# odbiornik.net
KiCad netlist of a schematic drawn in EAGLE
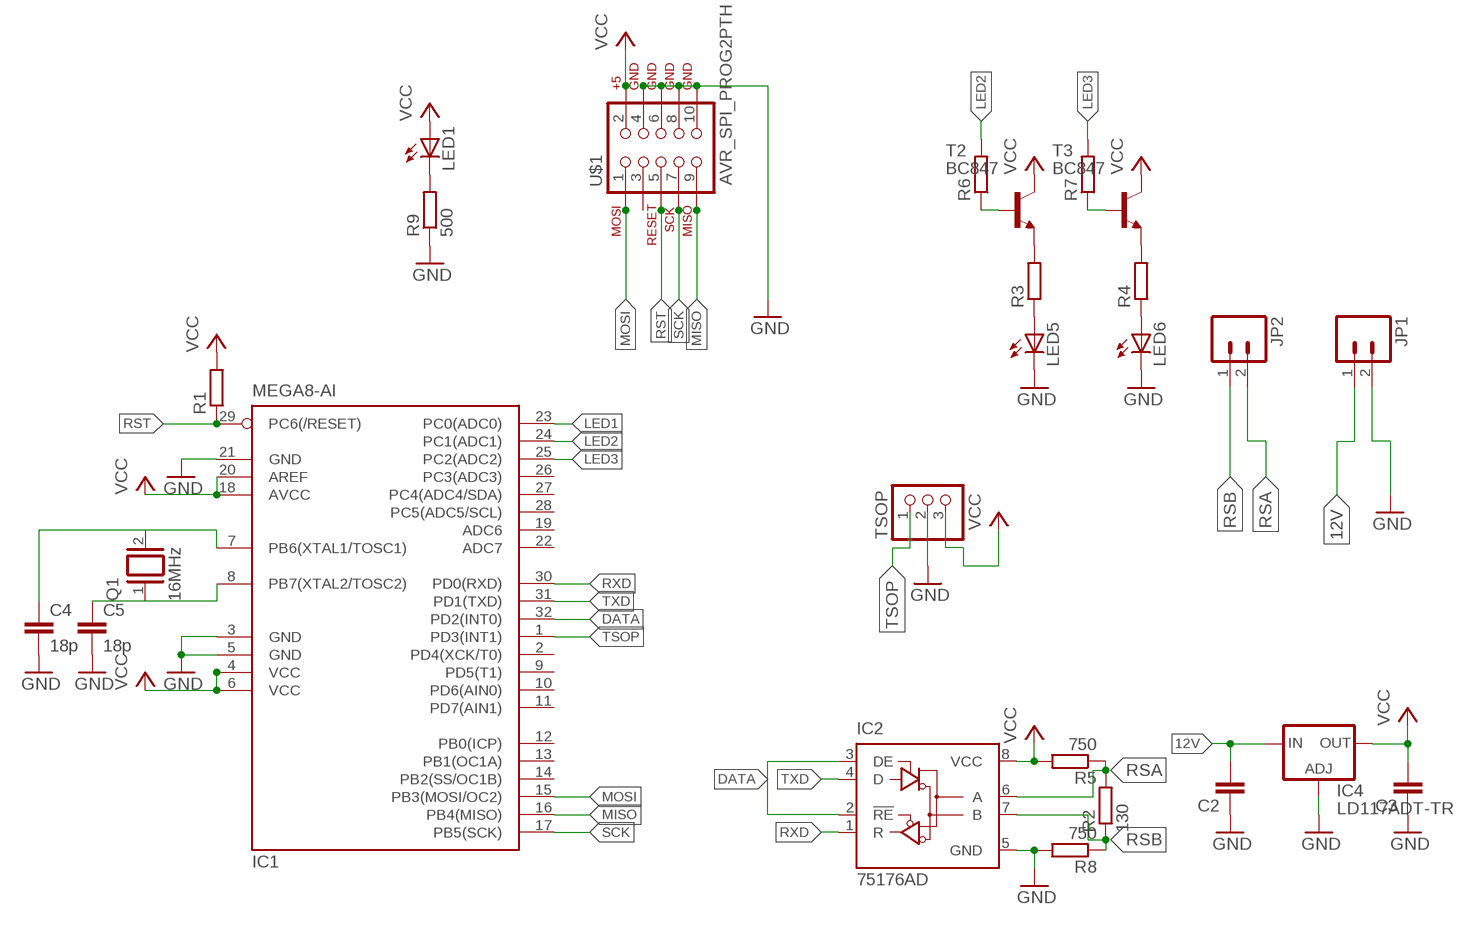
[diagram p0: schematic, sheet 1]

(export (version "E")
  (design (tool "Eeschema 10.0.6"))
  (components
    (comp (ref "C2")
      (value "C-EUC0805")
      (footprint "eagle-import:C0805")
      (libsource (lib "eagle-import") (part "C-EUC0805"))
    )
    (comp (ref "C3")
      (value "C-EUC0805")
      (footprint "eagle-import:C0805")
      (libsource (lib "eagle-import") (part "C-EUC0805"))
    )
    (comp (ref "C4")
      (value "18p")
      (footprint "eagle-import:C0805")
      (libsource (lib "eagle-import") (part "C-EUC0805"))
    )
    (comp (ref "C5")
      (value "18p")
      (footprint "eagle-import:C0805")
      (libsource (lib "eagle-import") (part "C-EUC0805"))
    )
    (comp (ref "IC1")
      (value "MEGA8-AI")
      (footprint "eagle-import:TQFP32-08")
      (fields (field (name "MPN") "ATMEGA8-16AU"))
      (libsource (lib "eagle-import") (part "MEGA8-AI"))
    )
    (comp (ref "IC2")
      (value "75176AD")
      (footprint "eagle-import:D_R-PDSO-G8")
      (libsource (lib "eagle-import") (part "75176AD"))
    )
    (comp (ref "IC4")
      (value "LD117ADT-TR")
      (footprint "eagle-import:DPACK")
      (libsource (lib "eagle-import") (part "LD117A?DT-TR"))
    )
    (comp (ref "JP1")
      (value "M02LOCK_LONGPADS")
      (footprint "eagle-import:1X02_LOCK_LONGPADS")
      (libsource (lib "eagle-import") (part "M02LOCK_LONGPADS"))
    )
    (comp (ref "JP2")
      (value "M02LOCK_LONGPADS")
      (footprint "eagle-import:1X02_LOCK_LONGPADS")
      (libsource (lib "eagle-import") (part "M02LOCK_LONGPADS"))
    )
    (comp (ref "LED1")
      (value "LED1206")
      (footprint "eagle-import:LED-1206")
      (libsource (lib "eagle-import") (part "LED1206"))
    )
    (comp (ref "LED5")
      (value "LEDSFH480")
      (footprint "eagle-import:SFH480")
      (libsource (lib "eagle-import") (part "LEDSFH480"))
    )
    (comp (ref "LED6")
      (value "LEDSFH480")
      (footprint "eagle-import:SFH480")
      (libsource (lib "eagle-import") (part "LEDSFH480"))
    )
    (comp (ref "Q1")
      (value "16MHz")
      (footprint "eagle-import:QS")
      (libsource (lib "eagle-import") (part "XTAL/S"))
    )
    (comp (ref "R1")
      (value "R-EU_R0805")
      (footprint "eagle-import:R0805")
      (libsource (lib "eagle-import") (part "R-EU_R0805"))
    )
    (comp (ref "R2")
      (value "130")
      (footprint "eagle-import:R0805")
      (libsource (lib "eagle-import") (part "R-EU_R0805"))
    )
    (comp (ref "R3")
      (value "R-EU_R0805")
      (footprint "eagle-import:R0805")
      (libsource (lib "eagle-import") (part "R-EU_R0805"))
    )
    (comp (ref "R4")
      (value "R-EU_R0805")
      (footprint "eagle-import:R0805")
      (libsource (lib "eagle-import") (part "R-EU_R0805"))
    )
    (comp (ref "R5")
      (value "750")
      (footprint "eagle-import:R0805")
      (libsource (lib "eagle-import") (part "R-EU_R0805"))
    )
    (comp (ref "R6")
      (value "R-EU_R0805")
      (footprint "eagle-import:R0805")
      (libsource (lib "eagle-import") (part "R-EU_R0805"))
    )
    (comp (ref "R7")
      (value "R-EU_R0805")
      (footprint "eagle-import:R0805")
      (libsource (lib "eagle-import") (part "R-EU_R0805"))
    )
    (comp (ref "R8")
      (value "750")
      (footprint "eagle-import:R0805")
      (libsource (lib "eagle-import") (part "R-EU_R0805"))
    )
    (comp (ref "R9")
      (value "500")
      (footprint "eagle-import:R0805")
      (libsource (lib "eagle-import") (part "R-EU_R0805"))
    )
    (comp (ref "T2")
      (value "BC847")
      (footprint "eagle-import:SOT23")
      (libsource (lib "eagle-import") (part "BC847"))
    )
    (comp (ref "T3")
      (value "BC847")
      (footprint "eagle-import:SOT23")
      (libsource (lib "eagle-import") (part "BC847"))
    )
    (comp (ref "TSOP")
      (value "PINHD-1X3")
      (footprint "eagle-import:1X03")
      (libsource (lib "eagle-import") (part "PINHD-1X3"))
    )
    (comp (ref "U$1")
      (value "AVR_SPI_PROG2PTH")
      (footprint "eagle-import:AVR_ICSP")
      (libsource (lib "eagle-import") (part "AVR_SPI_PROG2PTH"))
    )
  )
  (nets
    (net (code "1") (name "12V") (class "Default")
      (node (ref "C2") (pin "2") (pinfunction "2_2") (pintype "passive"))
      (node (ref "IC4") (pin "3") (pinfunction "IN_3") (pintype "input"))
      (node (ref "JP1") (pin "1") (pinfunction "1_1") (pintype "passive"))
    )
    (net (code "2") (name "DATA") (class "Default")
      (node (ref "IC1") (pin "32") (pinfunction "PD2(INT0)_32") (pintype "bidirectional"))
      (node (ref "IC2") (pin "2") (pinfunction "~{RE}_2") (pintype "input"))
      (node (ref "IC2") (pin "3") (pinfunction "DE_3") (pintype "input"))
    )
    (net (code "3") (name "GND") (class "Default")
      (node (ref "C2") (pin "1") (pinfunction "1_1") (pintype "passive"))
      (node (ref "C3") (pin "1") (pinfunction "1_1") (pintype "passive"))
      (node (ref "C4") (pin "2") (pinfunction "2_2") (pintype "passive"))
      (node (ref "C5") (pin "2") (pinfunction "2_2") (pintype "passive"))
      (node (ref "IC1") (pin "21") (pinfunction "GND_21") (pintype "power_in"))
      (node (ref "IC1") (pin "3") (pinfunction "GND_3") (pintype "power_in"))
      (node (ref "IC1") (pin "5") (pinfunction "GND_5") (pintype "power_in"))
      (node (ref "IC2") (pin "5") (pinfunction "GND_5") (pintype "power_in"))
      (node (ref "IC4") (pin "1") (pinfunction "ADJ_1") (pintype "input"))
      (node (ref "JP1") (pin "2") (pinfunction "2_2") (pintype "passive"))
      (node (ref "LED5") (pin "K") (pinfunction "C_K") (pintype "passive"))
      (node (ref "LED6") (pin "K") (pinfunction "C_K") (pintype "passive"))
      (node (ref "R8") (pin "2") (pinfunction "2_2") (pintype "passive"))
      (node (ref "R9") (pin "1") (pinfunction "1_1") (pintype "passive"))
      (node (ref "TSOP") (pin "2") (pinfunction "2_2") (pintype "passive"))
      (node (ref "U$1") (pin "10") (pinfunction "10_10") (pintype "passive"))
      (node (ref "U$1") (pin "4") (pinfunction "4_4") (pintype "passive"))
      (node (ref "U$1") (pin "6") (pinfunction "6_6") (pintype "passive"))
      (node (ref "U$1") (pin "8") (pinfunction "8_8") (pintype "passive"))
    )
    (net (code "4") (name "LED1") (class "Default")
      (node (ref "IC1") (pin "23") (pinfunction "PC0(ADC0)_23") (pintype "bidirectional"))
    )
    (net (code "5") (name "LED2") (class "Default")
      (node (ref "IC1") (pin "24") (pinfunction "PC1(ADC1)_24") (pintype "bidirectional"))
      (node (ref "R6") (pin "2") (pinfunction "2_2") (pintype "passive"))
    )
    (net (code "6") (name "LED3") (class "Default")
      (node (ref "IC1") (pin "25") (pinfunction "PC2(ADC2)_25") (pintype "bidirectional"))
      (node (ref "R7") (pin "2") (pinfunction "2_2") (pintype "passive"))
    )
    (net (code "7") (name "MISO") (class "Default")
      (node (ref "IC1") (pin "16") (pinfunction "PB4(MISO)_16") (pintype "bidirectional"))
      (node (ref "U$1") (pin "9") (pinfunction "9_9") (pintype "passive"))
    )
    (net (code "8") (name "MOSI") (class "Default")
      (node (ref "IC1") (pin "15") (pinfunction "PB3(MOSI/OC2)_15") (pintype "bidirectional"))
      (node (ref "U$1") (pin "1") (pinfunction "1_1") (pintype "passive"))
    )
    (net (code "9") (name "Net-(IC1-PB6(XTAL1{slash}TOSC1))") (class "Default")
      (node (ref "C4") (pin "1") (pinfunction "1_1") (pintype "passive"))
      (node (ref "IC1") (pin "7") (pinfunction "PB6(XTAL1/TOSC1)_7") (pintype "bidirectional"))
      (node (ref "Q1") (pin "2") (pinfunction "2_2") (pintype "passive"))
    )
    (net (code "10") (name "Net-(IC1-PB7(XTAL2{slash}TOSC2))") (class "Default")
      (node (ref "C5") (pin "1") (pinfunction "1_1") (pintype "passive"))
      (node (ref "IC1") (pin "8") (pinfunction "PB7(XTAL2/TOSC2)_8") (pintype "bidirectional"))
      (node (ref "Q1") (pin "1") (pinfunction "1_1") (pintype "passive"))
    )
    (net (code "11") (name "Net-(LED1-PadC)") (class "Default")
      (node (ref "LED1") (pin "C") (pinfunction "C_C") (pintype "passive"))
      (node (ref "R9") (pin "2") (pinfunction "2_2") (pintype "passive"))
    )
    (net (code "12") (name "Net-(LED5-PadA)") (class "Default")
      (node (ref "LED5") (pin "A") (pinfunction "A_A") (pintype "passive"))
      (node (ref "R3") (pin "1") (pinfunction "1_1") (pintype "passive"))
    )
    (net (code "13") (name "Net-(LED6-PadA)") (class "Default")
      (node (ref "LED6") (pin "A") (pinfunction "A_A") (pintype "passive"))
      (node (ref "R4") (pin "1") (pinfunction "1_1") (pintype "passive"))
    )
    (net (code "14") (name "Net-(T2-B)") (class "Default")
      (node (ref "R6") (pin "1") (pinfunction "1_1") (pintype "passive"))
      (node (ref "T2") (pin "1") (pinfunction "B_1") (pintype "passive"))
    )
    (net (code "15") (name "Net-(T2-E)") (class "Default")
      (node (ref "R3") (pin "2") (pinfunction "2_2") (pintype "passive"))
      (node (ref "T2") (pin "2") (pinfunction "E_2") (pintype "passive"))
    )
    (net (code "16") (name "Net-(T3-B)") (class "Default")
      (node (ref "R7") (pin "1") (pinfunction "1_1") (pintype "passive"))
      (node (ref "T3") (pin "1") (pinfunction "B_1") (pintype "passive"))
    )
    (net (code "17") (name "Net-(T3-E)") (class "Default")
      (node (ref "R4") (pin "2") (pinfunction "2_2") (pintype "passive"))
      (node (ref "T3") (pin "2") (pinfunction "E_2") (pintype "passive"))
    )
    (net (code "18") (name "RSA") (class "Default")
      (node (ref "IC2") (pin "6") (pinfunction "A_6") (pintype "output"))
      (node (ref "JP2") (pin "2") (pinfunction "2_2") (pintype "passive"))
      (node (ref "R2") (pin "2") (pinfunction "2_2") (pintype "passive"))
      (node (ref "R5") (pin "1") (pinfunction "1_1") (pintype "passive"))
    )
    (net (code "19") (name "RSB") (class "Default")
      (node (ref "IC2") (pin "7") (pinfunction "B_7") (pintype "output"))
      (node (ref "JP2") (pin "1") (pinfunction "1_1") (pintype "passive"))
      (node (ref "R2") (pin "1") (pinfunction "1_1") (pintype "passive"))
      (node (ref "R8") (pin "1") (pinfunction "1_1") (pintype "passive"))
    )
    (net (code "20") (name "RST") (class "Default")
      (node (ref "IC1") (pin "29") (pinfunction "PC6(/RESET)_29") (pintype "bidirectional"))
      (node (ref "R1") (pin "1") (pinfunction "1_1") (pintype "passive"))
      (node (ref "U$1") (pin "5") (pinfunction "5_5") (pintype "passive"))
    )
    (net (code "21") (name "RXD") (class "Default")
      (node (ref "IC1") (pin "30") (pinfunction "PD0(RXD)_30") (pintype "bidirectional"))
      (node (ref "IC2") (pin "1") (pinfunction "R_1") (pintype "input"))
    )
    (net (code "22") (name "SCK") (class "Default")
      (node (ref "IC1") (pin "17") (pinfunction "PB5(SCK)_17") (pintype "bidirectional"))
      (node (ref "U$1") (pin "7") (pinfunction "7_7") (pintype "passive"))
    )
    (net (code "23") (name "TSOP") (class "Default")
      (node (ref "IC1") (pin "1") (pinfunction "PD3(INT1)_1") (pintype "bidirectional"))
      (node (ref "TSOP") (pin "1") (pinfunction "1_1") (pintype "passive"))
    )
    (net (code "24") (name "TXD") (class "Default")
      (node (ref "IC1") (pin "31") (pinfunction "PD1(TXD)_31") (pintype "bidirectional"))
      (node (ref "IC2") (pin "4") (pinfunction "D_4") (pintype "input"))
    )
    (net (code "25") (name "VCC") (class "Default")
      (node (ref "C3") (pin "2") (pinfunction "2_2") (pintype "passive"))
      (node (ref "IC1") (pin "18") (pinfunction "AVCC_18") (pintype "power_in"))
      (node (ref "IC1") (pin "20") (pinfunction "AREF_20") (pintype "passive"))
      (node (ref "IC1") (pin "4") (pinfunction "VCC_4") (pintype "power_in"))
      (node (ref "IC1") (pin "6") (pinfunction "VCC_6") (pintype "power_in"))
      (node (ref "IC2") (pin "8") (pinfunction "VCC_8") (pintype "power_in"))
      (node (ref "IC4") (pin "4") (pinfunction "OUT_4") (pintype "passive"))
      (node (ref "LED1") (pin "A") (pinfunction "A_A") (pintype "passive"))
      (node (ref "R1") (pin "2") (pinfunction "2_2") (pintype "passive"))
      (node (ref "R5") (pin "2") (pinfunction "2_2") (pintype "passive"))
      (node (ref "T2") (pin "3") (pinfunction "C_3") (pintype "passive"))
      (node (ref "T3") (pin "3") (pinfunction "C_3") (pintype "passive"))
      (node (ref "TSOP") (pin "3") (pinfunction "3_3") (pintype "passive"))
      (node (ref "U$1") (pin "2") (pinfunction "2_2") (pintype "passive"))
    )
    (net (code "26") (name "unconnected-(IC1-ADC6-Pad19)") (class "Default")
      (node (ref "IC1") (pin "19") (pinfunction "ADC6_19") (pintype "bidirectional"))
    )
    (net (code "27") (name "unconnected-(IC1-ADC7-Pad22)") (class "Default")
      (node (ref "IC1") (pin "22") (pinfunction "ADC7_22") (pintype "bidirectional"))
    )
    (net (code "28") (name "unconnected-(IC1-PB0(ICP)-Pad12)") (class "Default")
      (node (ref "IC1") (pin "12") (pinfunction "PB0(ICP)_12") (pintype "bidirectional"))
    )
    (net (code "29") (name "unconnected-(IC1-PB1(OC1A)-Pad13)") (class "Default")
      (node (ref "IC1") (pin "13") (pinfunction "PB1(OC1A)_13") (pintype "bidirectional"))
    )
    (net (code "30") (name "unconnected-(IC1-PB2(SS{slash}OC1B)-Pad14)") (class "Default")
      (node (ref "IC1") (pin "14") (pinfunction "PB2(SS/OC1B)_14") (pintype "bidirectional"))
    )
    (net (code "31") (name "unconnected-(IC1-PC3(ADC3)-Pad26)") (class "Default")
      (node (ref "IC1") (pin "26") (pinfunction "PC3(ADC3)_26") (pintype "bidirectional"))
    )
    (net (code "32") (name "unconnected-(IC1-PC4(ADC4{slash}SDA)-Pad27)") (class "Default")
      (node (ref "IC1") (pin "27") (pinfunction "PC4(ADC4/SDA)_27") (pintype "bidirectional"))
    )
    (net (code "33") (name "unconnected-(IC1-PC5(ADC5{slash}SCL)-Pad28)") (class "Default")
      (node (ref "IC1") (pin "28") (pinfunction "PC5(ADC5/SCL)_28") (pintype "bidirectional"))
    )
    (net (code "34") (name "unconnected-(IC1-PD4(XCK{slash}T0)-Pad2)") (class "Default")
      (node (ref "IC1") (pin "2") (pinfunction "PD4(XCK/T0)_2") (pintype "bidirectional"))
    )
    (net (code "35") (name "unconnected-(IC1-PD5(T1)-Pad9)") (class "Default")
      (node (ref "IC1") (pin "9") (pinfunction "PD5(T1)_9") (pintype "bidirectional"))
    )
    (net (code "36") (name "unconnected-(IC1-PD6(AIN0)-Pad10)") (class "Default")
      (node (ref "IC1") (pin "10") (pinfunction "PD6(AIN0)_10") (pintype "bidirectional"))
    )
    (net (code "37") (name "unconnected-(IC1-PD7(AIN1)-Pad11)") (class "Default")
      (node (ref "IC1") (pin "11") (pinfunction "PD7(AIN1)_11") (pintype "bidirectional"))
    )
    (net (code "38") (name "unconnected-(U$1-Pad3)") (class "Default")
      (node (ref "U$1") (pin "3") (pinfunction "3_3") (pintype "passive"))
    )
  )
)
